# BMP388_Digital_Pressure_Sensor.net
KiCad netlist of a schematic drawn in Altium Designer
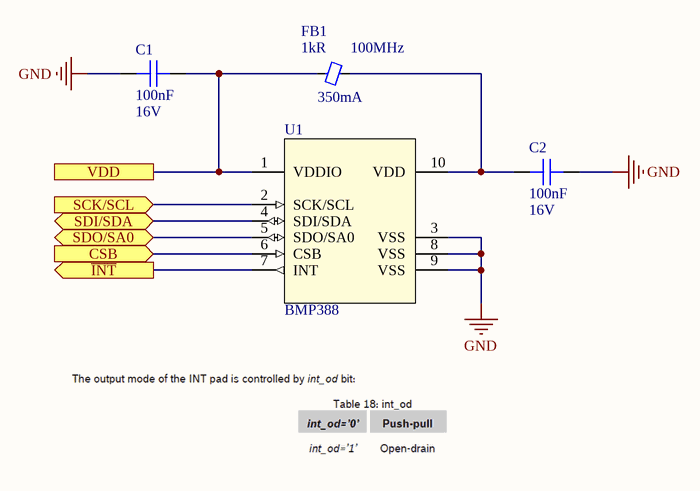
[diagram p0: BMP388_Digital_Pressure_Sensor.SchDoc]

(export (version "E")
  (design (tool "Eeschema 10.0.6"))
  (components
    (comp (ref "C1")
      (value "CAP CER 0.1UF 16V X7R 0402")
      (footprint "C0402")
      (description "0.1µF ±10% 16V Ceramic Capacitor X7R 0402 (1005 Metric)")
      (fields
        (field (name "MANUFACTURER PART NUMBER") "CC0402KRX7R7BB104")
        (field (name "MANUFACTURER") "YAGEO")
        (field (name "CAPACITANCE") "100nF")
        (field (name "VOLTAGE") "16V")
      )
      (libsource (lib "capacitors_smd") (part "CAP CER 0.1UF 16V X7R 0402"))
    )
    (comp (ref "C2")
      (value "CAP CER 0.1UF 16V X7R 0402")
      (footprint "C0402")
      (description "0.1µF ±10% 16V Ceramic Capacitor X7R 0402 (1005 Metric)")
      (fields
        (field (name "MANUFACTURER PART NUMBER") "CC0402KRX7R7BB104")
        (field (name "MANUFACTURER") "YAGEO")
        (field (name "CAPACITANCE") "100nF")
        (field (name "VOLTAGE") "16V")
      )
      (libsource (lib "capacitors_smd") (part "CAP CER 0.1UF 16V X7R 0402"))
    )
    (comp (ref "FB1")
      (value "FERRITE BEAD 1 KOHM 0402 1LN")
      (footprint "L0402")
      (description "1 kOhms @ 100MHz 1  Ferrite Bead 0402 (1005 Metric) 350mA 490mOhm")
      (fields
        (field (name "MANUFACTURER") "Murata")
        (field (name "MANUFACTURER PART NUMBER") "BLM15AX102SN1D")
        (field (name "IMPEDANCE") "1kR")
        (field (name "MAX DC CURRENT") "350mA")
        (field (name "TEST FREQUENCY") "100MHz")
      )
      (libsource (lib "ferrite_beads") (part "FERRITE BEAD 1 KOHM 0402 1LN"))
    )
    (comp (ref "U1")
      (value "BMP388")
      (footprint "QFN_BMP388_BOS")
      (description "Pressure Sensor 4.35PSI ~ 18.13PSI (30kPa ~ 125kPa) Absolute   10-WFLGA")
      (fields (field (name "MANUFACTURER") "Bosch Sensortec") (field (name "TOLERANCE") "20%"))
      (libsource (lib "BLDC_Motor_Driver") (part "IC BMP388 SENSOR PRESSURE ABS"))
    )
  )
  (nets
    (net (code "1") (name "/CSB") (class "Default")
      (node (ref "U1") (pin "6") (pinfunction "CSB_6") (pintype "input"))
    )
    (net (code "2") (name "/INT") (class "Default")
      (node (ref "U1") (pin "7") (pinfunction "INT_7") (pintype "output"))
    )
    (net (code "3") (name "/SCK{slash}SCL") (class "Default")
      (node (ref "U1") (pin "2") (pinfunction "SCK/SCL_2") (pintype "input"))
    )
    (net (code "4") (name "/SDI{slash}SDA") (class "Default")
      (node (ref "U1") (pin "4") (pinfunction "SDI/SDA_4") (pintype "bidirectional"))
    )
    (net (code "5") (name "/SDO{slash}SA0") (class "Default")
      (node (ref "U1") (pin "5") (pinfunction "SDO/SA0_5") (pintype "bidirectional"))
    )
    (net (code "6") (name "/VDD") (class "Default")
      (node (ref "C1") (pin "2") (pinfunction "2_2") (pintype "passive"))
      (node (ref "FB1") (pin "1") (pinfunction "1_1") (pintype "passive"))
      (node (ref "U1") (pin "1") (pinfunction "VDDIO_1") (pintype "power_in"))
    )
    (net (code "7") (name "GND") (class "Default")
      (node (ref "C1") (pin "1") (pinfunction "1_1") (pintype "passive"))
      (node (ref "C2") (pin "2") (pinfunction "2_2") (pintype "passive"))
      (node (ref "U1") (pin "3") (pinfunction "VSS_3") (pintype "power_in"))
      (node (ref "U1") (pin "8") (pinfunction "VSS_8") (pintype "power_in"))
      (node (ref "U1") (pin "9") (pinfunction "VSS_9") (pintype "power_in"))
    )
    (net (code "8") (name "Net-(U1-VDD)") (class "Default")
      (node (ref "C2") (pin "1") (pinfunction "1_1") (pintype "passive"))
      (node (ref "FB1") (pin "2") (pinfunction "2_2") (pintype "passive"))
      (node (ref "U1") (pin "10") (pinfunction "VDD_10") (pintype "power_in"))
    )
  )
)
